# 150555-1-Platino-v1_4.net
KiCad netlist of a schematic drawn in EAGLE
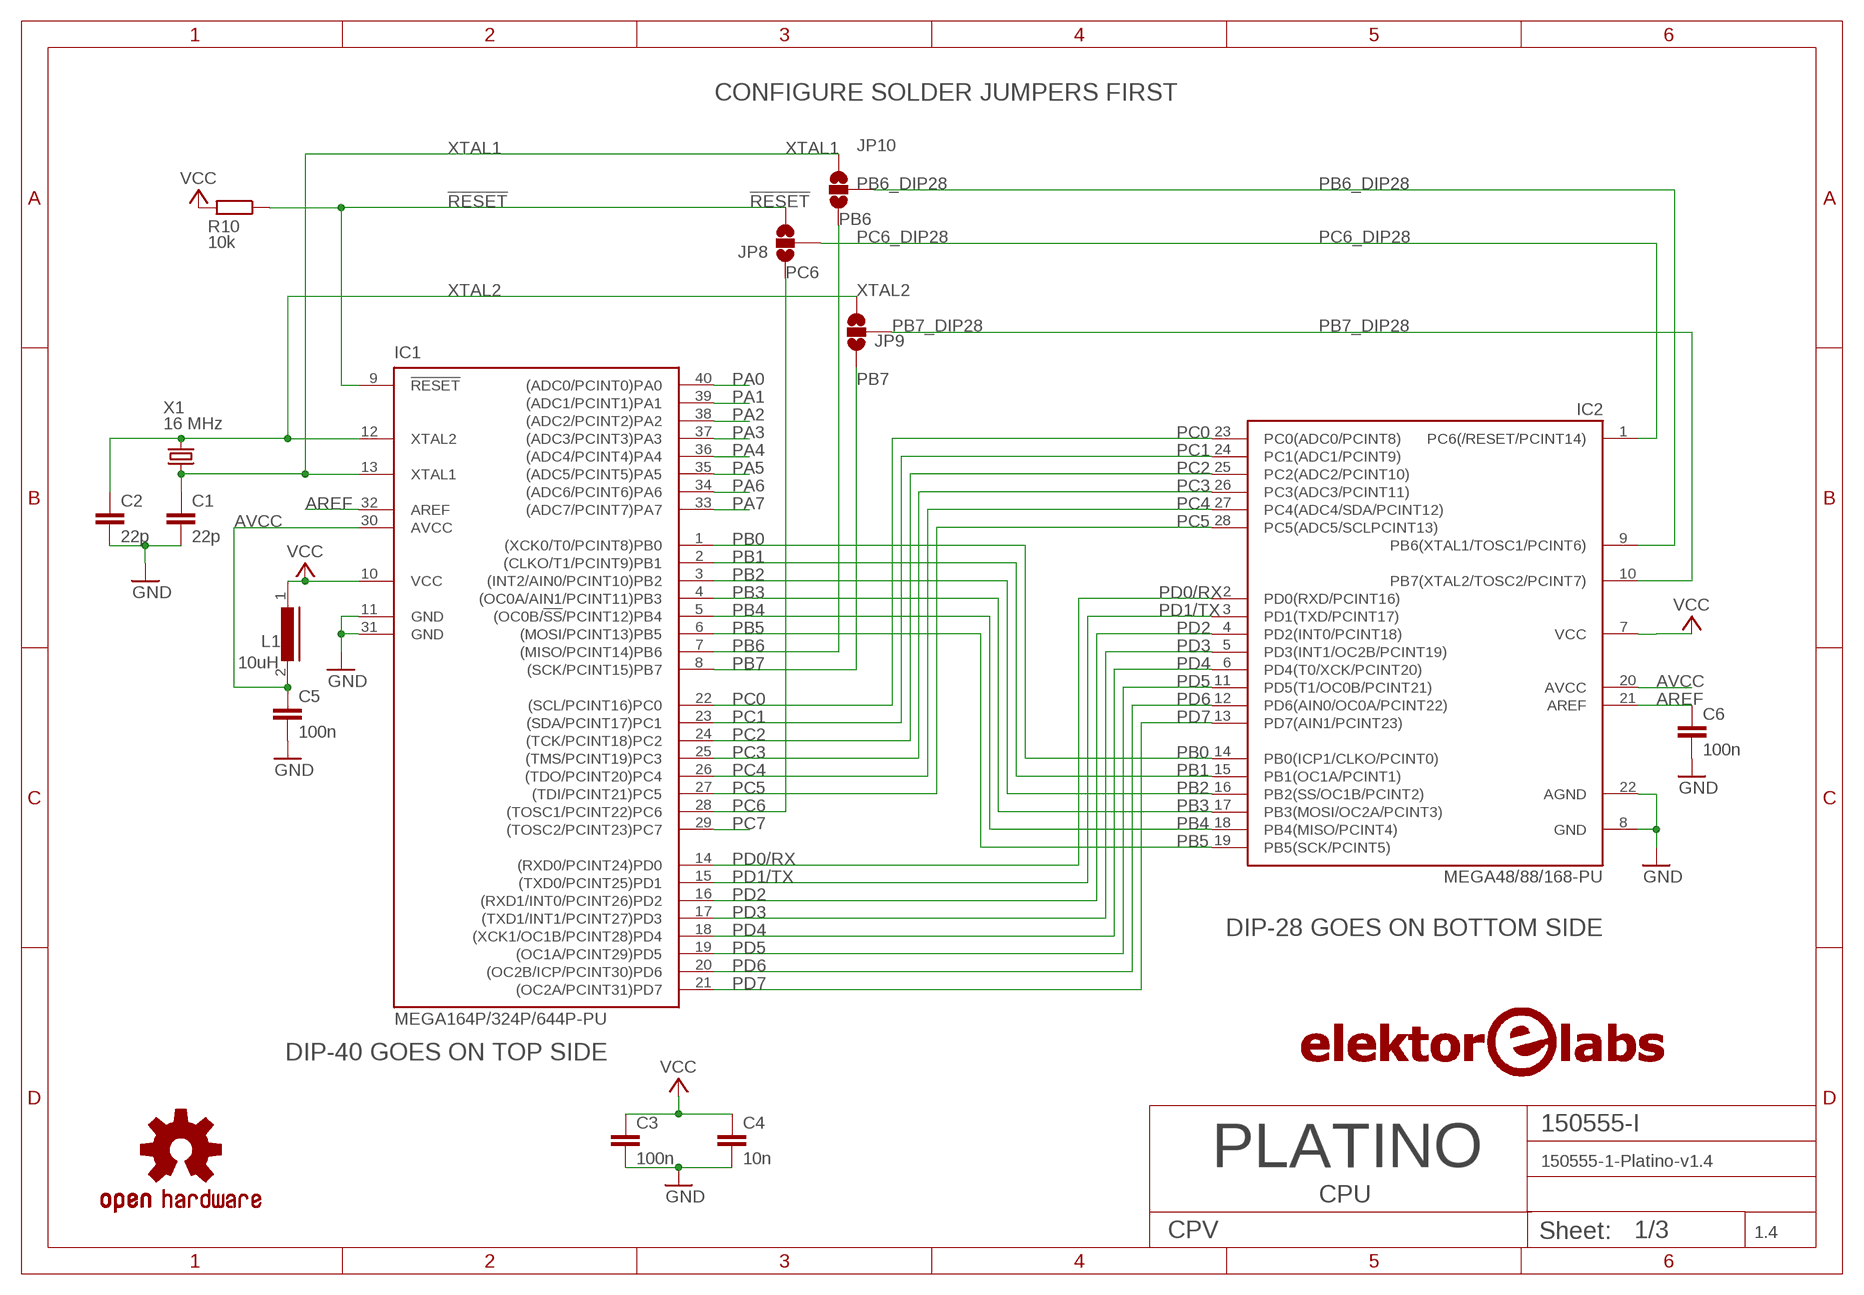
[diagram p0: schematic, sheet 1]
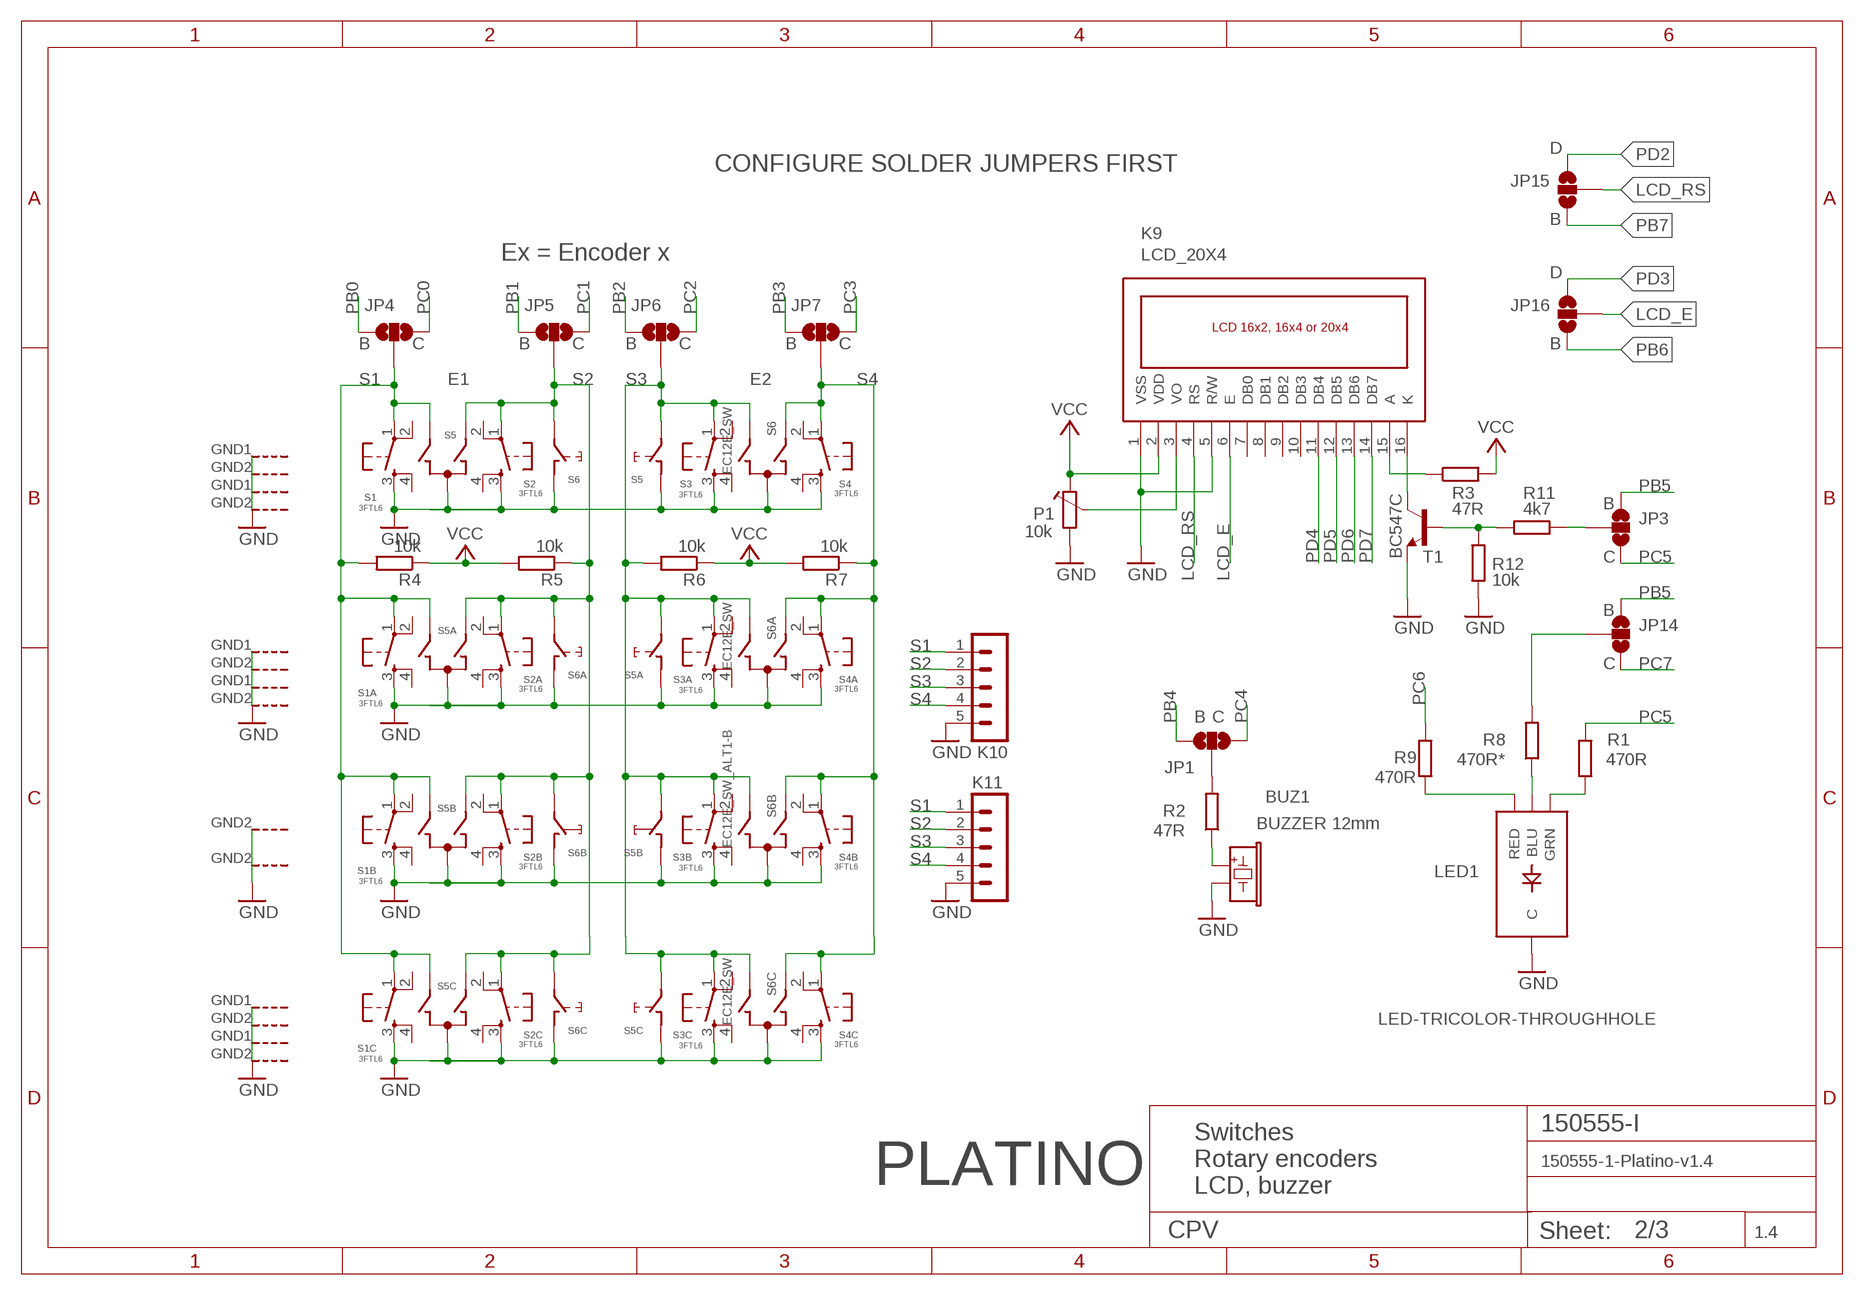
[diagram p1: schematic, sheet 2]
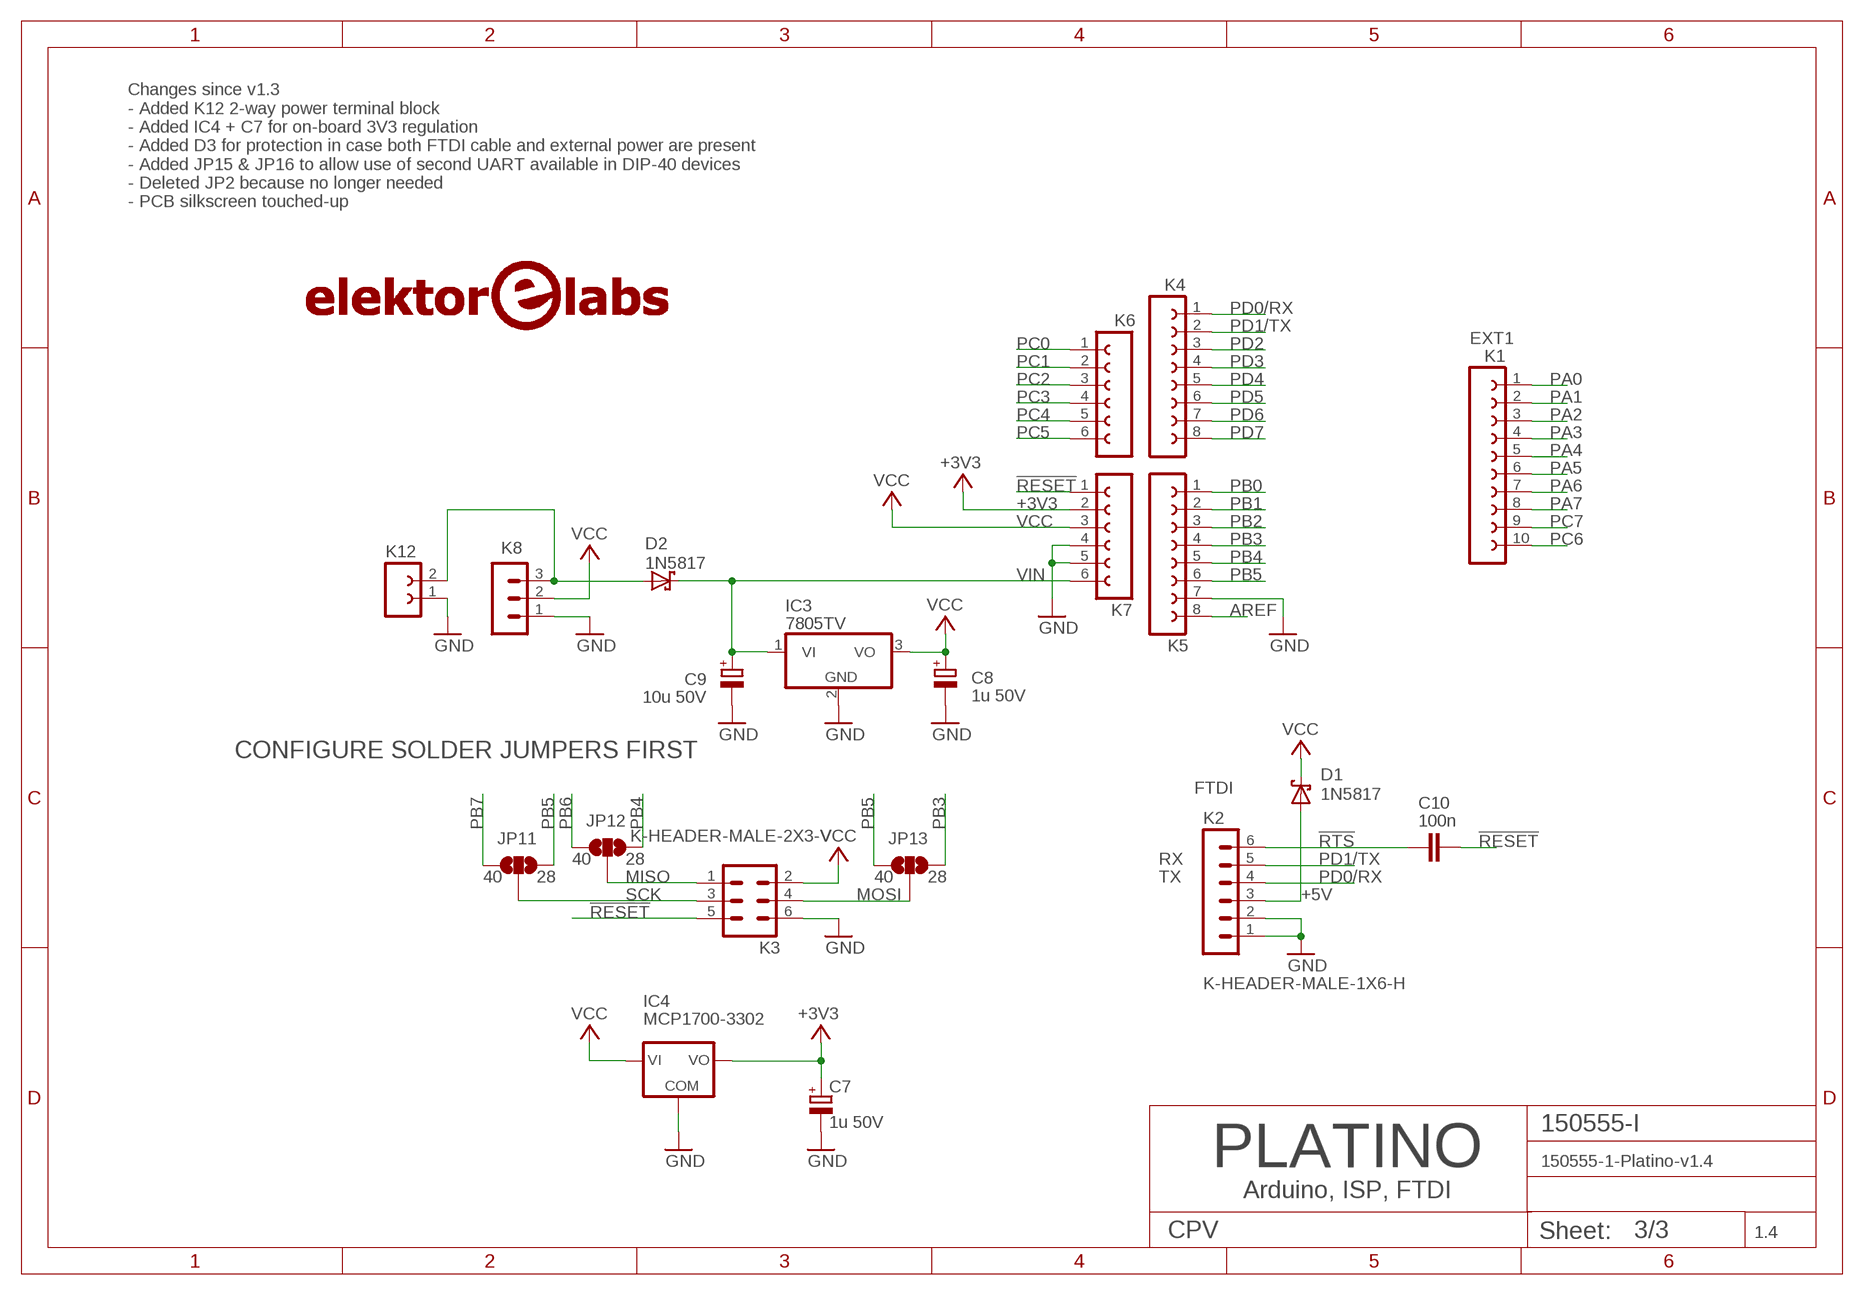
[diagram p2: schematic, sheet 3]

(export (version "E")
  (design (tool "Eeschema 10.0.6"))
  (components
    (comp (ref "C1")
      (value "22p")
      (footprint "eagle-import:ELPP-CNP-250")
      (libsource (lib "eagle-import") (part "C-NP--2.5MM22PF"))
    )
    (comp (ref "C2")
      (value "22p")
      (footprint "eagle-import:ELPP-CNP-250")
      (libsource (lib "eagle-import") (part "C-NP--2.5MM22PF"))
    )
    (comp (ref "C3")
      (value "100n")
      (footprint "eagle-import:ELPP-CNP-508")
      (libsource (lib "eagle-import") (part "C-NP--5.08MM100NF"))
    )
    (comp (ref "C4")
      (value "10n")
      (footprint "eagle-import:ELPP-CNP-254")
      (libsource (lib "eagle-import") (part "C-NP--2.54MM10NF"))
    )
    (comp (ref "C5")
      (value "100n")
      (footprint "eagle-import:ELPP-CNP-508")
      (libsource (lib "eagle-import") (part "C-NP--5.08MM100NF"))
    )
    (comp (ref "C6")
      (value "100n")
      (footprint "eagle-import:ELPP-CNP-508")
      (libsource (lib "eagle-import") (part "C-NP--5.08MM100NF"))
    )
    (comp (ref "IC1")
      (value "MEGA164P/324P/644P-PU")
      (footprint "eagle-import:DIL40")
      (libsource (lib "eagle-import") (part "MEGA164P/324P/644P-PU"))
    )
    (comp (ref "IC2")
      (value "MEGA48/88/168-PU")
      (footprint "eagle-import:DIL28-3")
      (libsource (lib "eagle-import") (part "MEGA48/88/168-PU"))
    )
    (comp (ref "JP8")
      (value "SOLDERJUMPER_2WAYT")
      (footprint "eagle-import:SJ_2")
      (libsource (lib "eagle-import") (part "SOLDERJUMPER_2WAYT"))
    )
    (comp (ref "JP9")
      (value "SOLDERJUMPER_2WAYT")
      (footprint "eagle-import:SJ_2")
      (libsource (lib "eagle-import") (part "SOLDERJUMPER_2WAYT"))
    )
    (comp (ref "JP10")
      (value "SOLDERJUMPER_2WAYT")
      (footprint "eagle-import:SJ_2")
      (libsource (lib "eagle-import") (part "SOLDERJUMPER_2WAYT"))
    )
    (comp (ref "L1")
      (value "10uH")
      (footprint "eagle-import:ELPP-L-0207-1000")
      (libsource (lib "eagle-import") (part "L--10MM10UH"))
    )
    (comp (ref "LOGO2")
      (value "LOGO-ELEKTOR-LABS-25MM")
      (footprint "eagle-import:EPP-LOGO-ELEKTOR-LABS-25MM")
      (libsource (lib "eagle-import") (part "LOGO-ELEKTOR-LABS-25MM"))
    )
    (comp (ref "R10")
      (value "10k")
      (footprint "eagle-import:ELPP-R-0207-1000")
      (libsource (lib "eagle-import") (part "R--10MM10K"))
    )
    (comp (ref "U$2")
      (value "OSHW-LOGOM")
      (footprint "eagle-import:OSHW-LOGO-M")
      (libsource (lib "eagle-import") (part "OSHW-LOGOM"))
    )
    (comp (ref "X1")
      (value "16 MHz")
      (footprint "eagle-import:ELPP-HC49")
      (libsource (lib "eagle-import") (part "X-CRYSTAL--16MHZ"))
    )
    (comp (ref "BUZ1")
      (value "BUZZER 12mm")
      (footprint "eagle-import:ELPP-BUZZER-12MM")
      (libsource (lib "eagle-import") (part "BUZ-BUZZER-12MM"))
    )
    (comp (ref "JP1")
      (value "SOLDERJUMPER_2WAYT")
      (footprint "eagle-import:SJ_2")
      (libsource (lib "eagle-import") (part "SOLDERJUMPER_2WAYT"))
    )
    (comp (ref "JP3")
      (value "SOLDERJUMPER_2WAYT")
      (footprint "eagle-import:SJ_2")
      (libsource (lib "eagle-import") (part "SOLDERJUMPER_2WAYT"))
    )
    (comp (ref "JP4")
      (value "SOLDERJUMPER_2WAYT")
      (footprint "eagle-import:SJ_2")
      (libsource (lib "eagle-import") (part "SOLDERJUMPER_2WAYT"))
    )
    (comp (ref "JP5")
      (value "SOLDERJUMPER_2WAYT")
      (footprint "eagle-import:SJ_2")
      (libsource (lib "eagle-import") (part "SOLDERJUMPER_2WAYT"))
    )
    (comp (ref "JP6")
      (value "SOLDERJUMPER_2WAYT")
      (footprint "eagle-import:SJ_2")
      (libsource (lib "eagle-import") (part "SOLDERJUMPER_2WAYT"))
    )
    (comp (ref "JP7")
      (value "SOLDERJUMPER_2WAYT")
      (footprint "eagle-import:SJ_2")
      (libsource (lib "eagle-import") (part "SOLDERJUMPER_2WAYT"))
    )
    (comp (ref "JP14")
      (value "SOLDERJUMPER_2WAYT")
      (footprint "eagle-import:SJ_2")
      (libsource (lib "eagle-import") (part "SOLDERJUMPER_2WAYT"))
    )
    (comp (ref "JP15")
      (value "SOLDERJUMPER_2WAYT")
      (footprint "eagle-import:SJ_2")
      (libsource (lib "eagle-import") (part "SOLDERJUMPER_2WAYT"))
    )
    (comp (ref "JP16")
      (value "SOLDERJUMPER_2WAYT")
      (footprint "eagle-import:SJ_2")
      (libsource (lib "eagle-import") (part "SOLDERJUMPER_2WAYT"))
    )
    (comp (ref "K9")
      (value "LCD_20X4")
      (footprint "eagle-import:LCD_MULTI2")
      (libsource (lib "eagle-import") (part "LCD_MULTI2"))
    )
    (comp (ref "K10")
      (value "K-HEADER-MALE-1X5-V")
      (footprint "eagle-import:ELPP-SIL-M-5-WAY")
      (libsource (lib "eagle-import") (part "K-HEADER-MALE-1X5-V"))
    )
    (comp (ref "K11")
      (value "K-HEADER-MALE-1X5-V")
      (footprint "eagle-import:ELPP-SIL-M-5-WAY")
      (libsource (lib "eagle-import") (part "K-HEADER-MALE-1X5-V"))
    )
    (comp (ref "LED1")
      (value "LED-TRICOLOR-THROUGHHOLE")
      (footprint "eagle-import:LED-TRICOLOR-THROUGHHOLE")
      (libsource (lib "eagle-import") (part "LED-TRICOLOR-THROUGHHOLE"))
    )
    (comp (ref "P1")
      (value "10k")
      (footprint "eagle-import:ELPP-TRIMMER-CB10-H")
      (libsource (lib "eagle-import") (part "P-TRIMMER--PT-1010K"))
    )
    (comp (ref "R1")
      (value "470R")
      (footprint "eagle-import:ELPP-R-0207-1000")
      (libsource (lib "eagle-import") (part "R--10MM470R"))
    )
    (comp (ref "R2")
      (value "47R")
      (footprint "eagle-import:ELPP-R-0207-1000")
      (libsource (lib "eagle-import") (part "R--10MM47R"))
    )
    (comp (ref "R3")
      (value "47R")
      (footprint "eagle-import:ELPP-R-0207-1000")
      (libsource (lib "eagle-import") (part "R--10MM47R"))
    )
    (comp (ref "R4")
      (value "10k")
      (footprint "eagle-import:ELPP-R-0207-1000")
      (libsource (lib "eagle-import") (part "R--10MM10K"))
    )
    (comp (ref "R5")
      (value "10k")
      (footprint "eagle-import:ELPP-R-0207-1000")
      (libsource (lib "eagle-import") (part "R--10MM10K"))
    )
    (comp (ref "R6")
      (value "10k")
      (footprint "eagle-import:ELPP-R-0207-1000")
      (libsource (lib "eagle-import") (part "R--10MM10K"))
    )
    (comp (ref "R7")
      (value "10k")
      (footprint "eagle-import:ELPP-R-0207-1000")
      (libsource (lib "eagle-import") (part "R--10MM10K"))
    )
    (comp (ref "R8")
      (value "470R*")
      (footprint "eagle-import:ELPP-R-0207-1000")
      (libsource (lib "eagle-import") (part "R--10MM470R"))
    )
    (comp (ref "R9")
      (value "470R")
      (footprint "eagle-import:ELPP-R-0207-1000")
      (libsource (lib "eagle-import") (part "R--10MM470R"))
    )
    (comp (ref "R11")
      (value "4k7")
      (footprint "eagle-import:ELPP-R-0207-1000")
      (libsource (lib "eagle-import") (part "R--10MM4K7"))
    )
    (comp (ref "R12")
      (value "10k")
      (footprint "eagle-import:ELPP-R-0207-1000")
      (libsource (lib "eagle-import") (part "R--10MM10K"))
    )
    (comp (ref "S1")
      (value "3FTL6")
      (footprint "eagle-import:PUSHBUTTON_MULTIMEC")
      (libsource (lib "eagle-import") (part "PUSHBUTTON_MULTIMEC"))
    )
    (comp (ref "S1A")
      (value "3FTL6")
      (footprint "eagle-import:PUSHBUTTON_MULTIMEC")
      (libsource (lib "eagle-import") (part "PUSHBUTTON_MULTIMEC"))
    )
    (comp (ref "S1B")
      (value "3FTL6")
      (footprint "eagle-import:PUSHBUTTON_MULTIMEC")
      (libsource (lib "eagle-import") (part "PUSHBUTTON_MULTIMEC"))
    )
    (comp (ref "S1C")
      (value "3FTL6")
      (footprint "eagle-import:PUSHBUTTON_MULTIMEC")
      (libsource (lib "eagle-import") (part "PUSHBUTTON_MULTIMEC"))
    )
    (comp (ref "S2")
      (value "3FTL6")
      (footprint "eagle-import:PUSHBUTTON_MULTIMEC")
      (libsource (lib "eagle-import") (part "PUSHBUTTON_MULTIMEC"))
    )
    (comp (ref "S2A")
      (value "3FTL6")
      (footprint "eagle-import:PUSHBUTTON_MULTIMEC")
      (libsource (lib "eagle-import") (part "PUSHBUTTON_MULTIMEC"))
    )
    (comp (ref "S2B")
      (value "3FTL6")
      (footprint "eagle-import:PUSHBUTTON_MULTIMEC")
      (libsource (lib "eagle-import") (part "PUSHBUTTON_MULTIMEC"))
    )
    (comp (ref "S2C")
      (value "3FTL6")
      (footprint "eagle-import:PUSHBUTTON_MULTIMEC")
      (libsource (lib "eagle-import") (part "PUSHBUTTON_MULTIMEC"))
    )
    (comp (ref "S3")
      (value "3FTL6")
      (footprint "eagle-import:PUSHBUTTON_MULTIMEC")
      (libsource (lib "eagle-import") (part "PUSHBUTTON_MULTIMEC"))
    )
    (comp (ref "S3A")
      (value "3FTL6")
      (footprint "eagle-import:PUSHBUTTON_MULTIMEC")
      (libsource (lib "eagle-import") (part "PUSHBUTTON_MULTIMEC"))
    )
    (comp (ref "S3B")
      (value "3FTL6")
      (footprint "eagle-import:PUSHBUTTON_MULTIMEC")
      (libsource (lib "eagle-import") (part "PUSHBUTTON_MULTIMEC"))
    )
    (comp (ref "S3C")
      (value "3FTL6")
      (footprint "eagle-import:PUSHBUTTON_MULTIMEC")
      (libsource (lib "eagle-import") (part "PUSHBUTTON_MULTIMEC"))
    )
    (comp (ref "S4")
      (value "3FTL6")
      (footprint "eagle-import:PUSHBUTTON_MULTIMEC")
      (libsource (lib "eagle-import") (part "PUSHBUTTON_MULTIMEC"))
    )
    (comp (ref "S4A")
      (value "3FTL6")
      (footprint "eagle-import:PUSHBUTTON_MULTIMEC")
      (libsource (lib "eagle-import") (part "PUSHBUTTON_MULTIMEC"))
    )
    (comp (ref "S4B")
      (value "3FTL6")
      (footprint "eagle-import:PUSHBUTTON_MULTIMEC")
      (libsource (lib "eagle-import") (part "PUSHBUTTON_MULTIMEC"))
    )
    (comp (ref "S4C")
      (value "3FTL6")
      (footprint "eagle-import:PUSHBUTTON_MULTIMEC")
      (libsource (lib "eagle-import") (part "PUSHBUTTON_MULTIMEC"))
    )
    (comp (ref "S5")
      (value "EC12E_SW")
      (footprint "eagle-import:ALPS_EC12E_SW")
      (fields (field (name "MPN") "EC12E2424407"))
      (libsource (lib "eagle-import") (part "EC12E_SW"))
    )
    (comp (ref "S5A")
      (value "EC12E_SW")
      (footprint "eagle-import:ALPS_EC12E_SW")
      (fields (field (name "MPN") "EC12E2424407"))
      (libsource (lib "eagle-import") (part "EC12E_SW"))
    )
    (comp (ref "S5B")
      (value "EC12E_SW_ALT1-B")
      (footprint "eagle-import:ALPS_EC12E_SW_ALT2")
      (libsource (lib "eagle-import") (part "EC12E_SW_ALT1-B"))
    )
    (comp (ref "S5C")
      (value "EC12E_SW")
      (footprint "eagle-import:ALPS_EC12E_SW")
      (fields (field (name "MPN") "EC12E2424407"))
      (libsource (lib "eagle-import") (part "EC12E_SW"))
    )
    (comp (ref "S6")
      (value "EC12E_SW")
      (footprint "eagle-import:ALPS_EC12E_SW")
      (fields (field (name "MPN") "EC12E2424407"))
      (libsource (lib "eagle-import") (part "EC12E_SW"))
    )
    (comp (ref "S6A")
      (value "EC12E_SW")
      (footprint "eagle-import:ALPS_EC12E_SW")
      (fields (field (name "MPN") "EC12E2424407"))
      (libsource (lib "eagle-import") (part "EC12E_SW"))
    )
    (comp (ref "S6B")
      (value "EC12E_SW_ALT1-B")
      (footprint "eagle-import:ALPS_EC12E_SW_ALT2")
      (libsource (lib "eagle-import") (part "EC12E_SW_ALT1-B"))
    )
    (comp (ref "S6C")
      (value "EC12E_SW")
      (footprint "eagle-import:ALPS_EC12E_SW")
      (fields (field (name "MPN") "EC12E2424407"))
      (libsource (lib "eagle-import") (part "EC12E_SW"))
    )
    (comp (ref "T1")
      (value "BC547C")
      (footprint "eagle-import:TO-92")
      (libsource (lib "eagle-import") (part "TRANSISTOR_NPNTO92"))
    )
    (comp (ref "C7")
      (value "1u 50V")
      (footprint "eagle-import:ELPP-CP-200-500")
      (libsource (lib "eagle-import") (part "C-POL--200-5001UF"))
    )
    (comp (ref "C8")
      (value "1u 50V")
      (footprint "eagle-import:ELPP-CP-200-500")
      (libsource (lib "eagle-import") (part "C-POL--200-5001UF"))
    )
    (comp (ref "C9")
      (value "10u 50V")
      (footprint "eagle-import:ELPP-CP-200-500")
      (libsource (lib "eagle-import") (part "C-POL--200-50010UF"))
    )
    (comp (ref "C10")
      (value "100n")
      (footprint "eagle-import:ELPP-CNP-508")
      (libsource (lib "eagle-import") (part "C-NP--5.08MM100NF"))
    )
    (comp (ref "D1")
      (value "1N5817")
      (footprint "eagle-import:ELPP-DO-41")
      (libsource (lib "eagle-import") (part "D-SCHOTTKY--D0411N5817"))
    )
    (comp (ref "D2")
      (value "1N5817")
      (footprint "eagle-import:ELPP-DO-41")
      (libsource (lib "eagle-import") (part "D-SCHOTTKY--D0411N5817"))
    )
    (comp (ref "IC3")
      (value "7805TV")
      (footprint "eagle-import:TO220V")
      (libsource (lib "eagle-import") (part "78TV05"))
    )
    (comp (ref "IC4")
      (value "MCP1700-3302")
      (footprint "eagle-import:ELPP-TO-92")
      (libsource (lib "eagle-import") (part "IC-REGULATOR--MCP17003V3"))
    )
    (comp (ref "JP11")
      (value "SOLDERJUMPER_2WAYT")
      (footprint "eagle-import:SJ_2")
      (libsource (lib "eagle-import") (part "SOLDERJUMPER_2WAYT"))
    )
    (comp (ref "JP12")
      (value "SOLDERJUMPER_2WAYT")
      (footprint "eagle-import:SJ_2")
      (libsource (lib "eagle-import") (part "SOLDERJUMPER_2WAYT"))
    )
    (comp (ref "JP13")
      (value "SOLDERJUMPER_2WAYT")
      (footprint "eagle-import:SJ_2")
      (libsource (lib "eagle-import") (part "SOLDERJUMPER_2WAYT"))
    )
    (comp (ref "K1")
      (value "EXT1")
      (footprint "eagle-import:ELPP-SIL-F-10-WAY")
      (libsource (lib "eagle-import") (part "K-HEADER-FEMALE-1X10-V"))
    )
    (comp (ref "K2")
      (value "K-HEADER-MALE-1X6-H")
      (footprint "eagle-import:ELPP-SIL-M-6-WAY-90DEG")
      (libsource (lib "eagle-import") (part "K-HEADER-MALE-1X6-H"))
    )
    (comp (ref "K3")
      (value "K-HEADER-MALE-2X3-V")
      (footprint "eagle-import:ELPP-DIL-M-6-WAY-V")
      (libsource (lib "eagle-import") (part "K-HEADER-MALE-2X3-V"))
    )
    (comp (ref "K4")
      (value "K-HEADER-FEMALE-1X8-V")
      (footprint "eagle-import:ELPP-SIL-F-8-WAY")
      (libsource (lib "eagle-import") (part "K-HEADER-FEMALE-1X8-V"))
    )
    (comp (ref "K5")
      (value "K-HEADER-FEMALE-1X8-V")
      (footprint "eagle-import:ELPP-SIL-F-8-WAY")
      (libsource (lib "eagle-import") (part "K-HEADER-FEMALE-1X8-V"))
    )
    (comp (ref "K6")
      (value "K-HEADER-FEMALE-1X6-V")
      (footprint "eagle-import:ELPP-SIL-F-6-WAY")
      (libsource (lib "eagle-import") (part "K-HEADER-FEMALE-1X6-V"))
    )
    (comp (ref "K7")
      (value "K-HEADER-FEMALE-1X6-V")
      (footprint "eagle-import:ELPP-SIL-F-6-WAY")
      (libsource (lib "eagle-import") (part "K-HEADER-FEMALE-1X6-V"))
    )
    (comp (ref "K8")
      (value "K-HEADER-MALE-1X3-V")
      (footprint "eagle-import:ELPP-SIL-M-3-WAY")
      (libsource (lib "eagle-import") (part "K-HEADER-MALE-1X3-V"))
    )
    (comp (ref "K12")
      (value "K-TERMINAL-BLOCK-1X2-350")
      (footprint "eagle-import:ELPP-TB-350-2")
      (libsource (lib "eagle-import") (part "K-TERMINAL-BLOCK-1X2-350"))
    )
    (comp (ref "LOGO1")
      (value "LOGO-ELEKTOR-LABS-25MM")
      (footprint "eagle-import:EPP-LOGO-ELEKTOR-LABS-25MM")
      (libsource (lib "eagle-import") (part "LOGO-ELEKTOR-LABS-25MM"))
    )
  )
  (nets
    (net (code "1") (name "+3V3") (class "Default")
      (node (ref "C7") (pin "+") (pinfunction "+_+") (pintype "passive"))
      (node (ref "IC4") (pin "3") (pinfunction "VO_3") (pintype "passive"))
      (node (ref "K7") (pin "2") (pinfunction "2_2") (pintype "passive"))
    )
    (net (code "2") (name "+5V") (class "Default")
      (node (ref "D1") (pin "A") (pinfunction "A_A") (pintype "passive"))
      (node (ref "K2") (pin "3") (pinfunction "3_3") (pintype "passive"))
    )
    (net (code "3") (name "AREF") (class "Default")
      (node (ref "C6") (pin "1") (pinfunction "1_1") (pintype "passive"))
      (node (ref "IC1") (pin "32") (pinfunction "AREF_32") (pintype "power_in"))
      (node (ref "IC2") (pin "21") (pinfunction "AREF_21") (pintype "passive"))
      (node (ref "K5") (pin "8") (pinfunction "8_8") (pintype "passive"))
    )
    (net (code "4") (name "AVCC") (class "Default")
      (node (ref "C5") (pin "1") (pinfunction "1_1") (pintype "passive"))
      (node (ref "IC1") (pin "30") (pinfunction "AVCC_30") (pintype "power_in"))
      (node (ref "IC2") (pin "20") (pinfunction "AVCC_20") (pintype "passive"))
      (node (ref "L1") (pin "2") (pinfunction "2_2") (pintype "passive"))
    )
    (net (code "5") (name "GND") (class "Default")
      (node (ref "BUZ1") (pin "-") (pinfunction "2_-") (pintype "passive"))
      (node (ref "C1") (pin "2") (pinfunction "2_2") (pintype "passive"))
      (node (ref "C2") (pin "2") (pinfunction "2_2") (pintype "passive"))
      (node (ref "C3") (pin "2") (pinfunction "2_2") (pintype "passive"))
      (node (ref "C4") (pin "2") (pinfunction "2_2") (pintype "passive"))
      (node (ref "C5") (pin "2") (pinfunction "2_2") (pintype "passive"))
      (node (ref "C6") (pin "2") (pinfunction "2_2") (pintype "passive"))
      (node (ref "C7") (pin "-") (pinfunction "-_-") (pintype "passive"))
      (node (ref "C8") (pin "-") (pinfunction "-_-") (pintype "passive"))
      (node (ref "C9") (pin "-") (pinfunction "-_-") (pintype "passive"))
      (node (ref "IC1") (pin "11") (pinfunction "GND_11") (pintype "power_in"))
      (node (ref "IC1") (pin "31") (pinfunction "GND_31") (pintype "power_in"))
      (node (ref "IC2") (pin "22") (pinfunction "AGND_22") (pintype "power_in"))
      (node (ref "IC2") (pin "8") (pinfunction "GND_8") (pintype "power_in"))
      (node (ref "IC3") (pin "2") (pinfunction "GND_2") (pintype "passive"))
      (node (ref "IC4") (pin "1") (pinfunction "COM_1") (pintype "input"))
      (node (ref "K10") (pin "5") (pinfunction "5_5") (pintype "passive"))
      (node (ref "K11") (pin "5") (pinfunction "5_5") (pintype "passive"))
      (node (ref "K12") (pin "1") (pinfunction "1_1") (pintype "passive"))
      (node (ref "K2") (pin "1") (pinfunction "1_1") (pintype "passive"))
      (node (ref "K2") (pin "2") (pinfunction "2_2") (pintype "passive"))
      (node (ref "K3") (pin "6") (pinfunction "6_6") (pintype "passive"))
      (node (ref "K5") (pin "7") (pinfunction "7_7") (pintype "passive"))
      (node (ref "K7") (pin "4") (pinfunction "4_4") (pintype "passive"))
      (node (ref "K7") (pin "5") (pinfunction "5_5") (pintype "passive"))
      (node (ref "K8") (pin "1") (pinfunction "1_1") (pintype "passive"))
      (node (ref "K9") (pin "1") (pinfunction "VSS_1") (pintype "power_in"))
      (node (ref "K9") (pin "5") (pinfunction "R/W_5") (pintype "input"))
      (node (ref "LED1") (pin "GND") (pinfunction "C_GND") (pintype "bidirectional"))
      (node (ref "P1") (pin "1") (pinfunction "1_1") (pintype "passive"))
      (node (ref "R12") (pin "1") (pinfunction "1_1") (pintype "passive"))
      (node (ref "S1") (pin "3") (pinfunction "3_3") (pintype "passive"))
      (node (ref "S1A") (pin "3") (pinfunction "3_3") (pintype "passive"))
      (node (ref "S1B") (pin "3") (pinfunction "3_3") (pintype "passive"))
      (node (ref "S1C") (pin "3") (pinfunction "3_3") (pintype "passive"))
      (node (ref "S2") (pin "3") (pinfunction "3_3") (pintype "passive"))
      (node (ref "S2A") (pin "3") (pinfunction "3_3") (pintype "passive"))
      (node (ref "S2B") (pin "3") (pinfunction "3_3") (pintype "passive"))
      (node (ref "S2C") (pin "3") (pinfunction "3_3") (pintype "passive"))
      (node (ref "S3") (pin "3") (pinfunction "3_3") (pintype "passive"))
      (node (ref "S3A") (pin "3") (pinfunction "3_3") (pintype "passive"))
      (node (ref "S3B") (pin "3") (pinfunction "3_3") (pintype "passive"))
      (node (ref "S3C") (pin "3") (pinfunction "3_3") (pintype "passive"))
      (node (ref "S4") (pin "3") (pinfunction "3_3") (pintype "passive"))
      (node (ref "S4A") (pin "3") (pinfunction "3_3") (pintype "passive"))
      (node (ref "S4B") (pin "3") (pinfunction "3_3") (pintype "passive"))
      (node (ref "S4C") (pin "3") (pinfunction "3_3") (pintype "passive"))
      (node (ref "S5") (pin "C") (pinfunction "C_C") (pintype "passive"))
      (node (ref "S5") (pin "D") (pinfunction "1_D") (pintype "passive"))
      (node (ref "S5") (pin "GND1") (pinfunction "G_GND1") (pintype "passive"))
      (node (ref "S5") (pin "GND2") (pinfunction "G_GND2") (pintype "passive"))
      (node (ref "S5A") (pin "C") (pinfunction "C_C") (pintype "passive"))
      (node (ref "S5A") (pin "D") (pinfunction "1_D") (pintype "passive"))
      (node (ref "S5A") (pin "GND1") (pinfunction "G_GND1") (pintype "passive"))
      (node (ref "S5A") (pin "GND2") (pinfunction "G_GND2") (pintype "passive"))
      (node (ref "S5B") (pin "C") (pinfunction "C_C") (pintype "passive"))
      (node (ref "S5B") (pin "D") (pinfunction "1_D") (pintype "passive"))
      (node (ref "S5B") (pin "GND2") (pinfunction "G_GND2") (pintype "passive"))
      (node (ref "S5C") (pin "C") (pinfunction "C_C") (pintype "passive"))
      (node (ref "S5C") (pin "D") (pinfunction "1_D") (pintype "passive"))
      (node (ref "S5C") (pin "GND1") (pinfunction "G_GND1") (pintype "passive"))
      (node (ref "S5C") (pin "GND2") (pinfunction "G_GND2") (pintype "passive"))
      (node (ref "S6") (pin "C") (pinfunction "C_C") (pintype "passive"))
      (node (ref "S6") (pin "D") (pinfunction "1_D") (pintype "passive"))
      (node (ref "S6") (pin "GND1") (pinfunction "G_GND1") (pintype "passive"))
      (node (ref "S6") (pin "GND2") (pinfunction "G_GND2") (pintype "passive"))
      (node (ref "S6A") (pin "C") (pinfunction "C_C") (pintype "passive"))
      (node (ref "S6A") (pin "D") (pinfunction "1_D") (pintype "passive"))
      (node (ref "S6A") (pin "GND1") (pinfunction "G_GND1") (pintype "passive"))
      (node (ref "S6A") (pin "GND2") (pinfunction "G_GND2") (pintype "passive"))
      (node (ref "S6B") (pin "C") (pinfunction "C_C") (pintype "passive"))
      (node (ref "S6B") (pin "D") (pinfunction "1_D") (pintype "passive"))
      (node (ref "S6B") (pin "GND2") (pinfunction "G_GND2") (pintype "passive"))
      (node (ref "S6C") (pin "C") (pinfunction "C_C") (pintype "passive"))
      (node (ref "S6C") (pin "D") (pinfunction "1_D") (pintype "passive"))
      (node (ref "S6C") (pin "GND1") (pinfunction "G_GND1") (pintype "passive"))
      (node (ref "S6C") (pin "GND2") (pinfunction "G_GND2") (pintype "passive"))
      (node (ref "T1") (pin "1") (pinfunction "E_1") (pintype "passive"))
    )
    (net (code "6") (name "LCD_E") (class "Default")
      (node (ref "JP16") (pin "2") (pinfunction "2_2") (pintype "passive"))
      (node (ref "K9") (pin "6") (pinfunction "E_6") (pintype "input"))
    )
    (net (code "7") (name "LCD_RS") (class "Default")
      (node (ref "JP15") (pin "2") (pinfunction "2_2") (pintype "passive"))
      (node (ref "K9") (pin "4") (pinfunction "RS_4") (pintype "input"))
    )
    (net (code "8") (name "MISO") (class "Default")
      (node (ref "JP12") (pin "2") (pinfunction "2_2") (pintype "passive"))
      (node (ref "K3") (pin "1") (pinfunction "1_1") (pintype "passive"))
    )
    (net (code "9") (name "MOSI") (class "Default")
      (node (ref "JP13") (pin "2") (pinfunction "2_2") (pintype "passive"))
      (node (ref "K3") (pin "4") (pinfunction "4_4") (pintype "passive"))
    )
    (net (code "10") (name "Net-(BUZ1-1)") (class "Default")
      (node (ref "BUZ1") (pin "+") (pinfunction "1_+") (pintype "passive"))
      (node (ref "R2") (pin "1") (pinfunction "1_1") (pintype "passive"))
    )
    (net (code "11") (name "Net-(D2-PadA)") (class "Default")
      (node (ref "D2") (pin "A") (pinfunction "A_A") (pintype "passive"))
      (node (ref "K12") (pin "2") (pinfunction "2_2") (pintype "passive"))
      (node (ref "K8") (pin "3") (pinfunction "3_3") (pintype "passive"))
    )
    (net (code "12") (name "Net-(JP1-Pad2)") (class "Default")
      (node (ref "JP1") (pin "2") (pinfunction "2_2") (pintype "passive"))
      (node (ref "R2") (pin "2") (pinfunction "2_2") (pintype "passive"))
    )
    (net (code "13") (name "Net-(JP3-Pad2)") (class "Default")
      (node (ref "JP3") (pin "2") (pinfunction "2_2") (pintype "passive"))
      (node (ref "R11") (pin "2") (pinfunction "2_2") (pintype "passive"))
    )
    (net (code "14") (name "Net-(JP14-Pad2)") (class "Default")
      (node (ref "JP14") (pin "2") (pinfunction "2_2") (pintype "passive"))
      (node (ref "R8") (pin "2") (pinfunction "2_2") (pintype "passive"))
    )
    (net (code "15") (name "Net-(K9-A)") (class "Default")
      (node (ref "K9") (pin "15") (pinfunction "A_15") (pintype "passive"))
      (node (ref "R3") (pin "1") (pinfunction "1_1") (pintype "passive"))
    )
    (net (code "16") (name "Net-(K9-K)") (class "Default")
      (node (ref "K9") (pin "16") (pinfunction "K_16") (pintype "passive"))
      (node (ref "T1") (pin "3") (pinfunction "C_3") (pintype "passive"))
    )
    (net (code "17") (name "Net-(K9-VO)") (class "Default")
      (node (ref "K9") (pin "3") (pinfunction "VO_3") (pintype "passive"))
      (node (ref "P1") (pin "3") (pinfunction "3_3") (pintype "passive"))
    )
    (net (code "18") (name "Net-(LED1-PadBLU)") (class "Default")
      (node (ref "LED1") (pin "BLU") (pinfunction "BLU_BLU") (pintype "bidirectional"))
      (node (ref "R8") (pin "1") (pinfunction "1_1") (pintype "passive"))
    )
    (net (code "19") (name "Net-(LED1-PadGRN)") (class "Default")
      (node (ref "LED1") (pin "GRN") (pinfunction "GRN_GRN") (pintype "bidirectional"))
      (node (ref "R1") (pin "1") (pinfunction "1_1") (pintype "passive"))
    )
    (net (code "20") (name "Net-(LED1-PadRED)") (class "Default")
      (node (ref "LED1") (pin "RED") (pinfunction "RED_RED") (pintype "bidirectional"))
      (node (ref "R9") (pin "1") (pinfunction "1_1") (pintype "passive"))
    )
    (net (code "21") (name "Net-(T1-B)") (class "Default")
      (node (ref "R11") (pin "1") (pinfunction "1_1") (pintype "passive"))
      (node (ref "R12") (pin "2") (pinfunction "2_2") (pintype "passive"))
      (node (ref "T1") (pin "2") (pinfunction "B_2") (pintype "passive"))
    )
    (net (code "22") (name "PA0") (class "Default")
      (node (ref "IC1") (pin "40") (pinfunction "(ADC0/PCINT0)PA0_40") (pintype "bidirectional"))
      (node (ref "K1") (pin "1") (pinfunction "1_1") (pintype "passive"))
    )
    (net (code "23") (name "PA1") (class "Default")
      (node (ref "IC1") (pin "39") (pinfunction "(ADC1/PCINT1)PA1_39") (pintype "bidirectional"))
      (node (ref "K1") (pin "2") (pinfunction "2_2") (pintype "passive"))
    )
    (net (code "24") (name "PA2") (class "Default")
      (node (ref "IC1") (pin "38") (pinfunction "(ADC2/PCINT2)PA2_38") (pintype "bidirectional"))
      (node (ref "K1") (pin "3") (pinfunction "3_3") (pintype "passive"))
    )
    (net (code "25") (name "PA3") (class "Default")
      (node (ref "IC1") (pin "37") (pinfunction "(ADC3/PCINT3)PA3_37") (pintype "bidirectional"))
      (node (ref "K1") (pin "4") (pinfunction "4_4") (pintype "passive"))
    )
    (net (code "26") (name "PA4") (class "Default")
      (node (ref "IC1") (pin "36") (pinfunction "(ADC4/PCINT4)PA4_36") (pintype "bidirectional"))
      (node (ref "K1") (pin "5") (pinfunction "5_5") (pintype "passive"))
    )
    (net (code "27") (name "PA5") (class "Default")
      (node (ref "IC1") (pin "35") (pinfunction "(ADC5/PCINT5)PA5_35") (pintype "bidirectional"))
      (node (ref "K1") (pin "6") (pinfunction "6_6") (pintype "passive"))
    )
    (net (code "28") (name "PA6") (class "Default")
      (node (ref "IC1") (pin "34") (pinfunction "(ADC6/PCINT6)PA6_34") (pintype "bidirectional"))
      (node (ref "K1") (pin "7") (pinfunction "7_7") (pintype "passive"))
    )
    (net (code "29") (name "PA7") (class "Default")
      (node (ref "IC1") (pin "33") (pinfunction "(ADC7/PCINT7)PA7_33") (pintype "bidirectional"))
      (node (ref "K1") (pin "8") (pinfunction "8_8") (pintype "passive"))
    )
    (net (code "30") (name "PB0") (class "Default")
      (node (ref "IC1") (pin "1") (pinfunction "(XCK0/T0/PCINT8)PB0_1") (pintype "bidirectional"))
      (node (ref "IC2") (pin "14") (pinfunction "PB0(ICP1/CLKO/PCINT0)_14") (pintype "bidirectional"))
      (node (ref "JP4") (pin "1") (pinfunction "1_1") (pintype "passive"))
      (node (ref "K5") (pin "1") (pinfunction "1_1") (pintype "passive"))
    )
    (net (code "31") (name "PB1") (class "Default")
      (node (ref "IC1") (pin "2") (pinfunction "(CLKO/T1/PCINT9)PB1_2") (pintype "bidirectional"))
      (node (ref "IC2") (pin "15") (pinfunction "PB1(OC1A/PCINT1)_15") (pintype "bidirectional"))
      (node (ref "JP5") (pin "1") (pinfunction "1_1") (pintype "passive"))
      (node (ref "K5") (pin "2") (pinfunction "2_2") (pintype "passive"))
    )
    (net (code "32") (name "PB2") (class "Default")
      (node (ref "IC1") (pin "3") (pinfunction "(INT2/AIN0/PCINT10)PB2_3") (pintype "bidirectional"))
      (node (ref "IC2") (pin "16") (pinfunction "PB2(SS/OC1B/PCINT2)_16") (pintype "bidirectional"))
      (node (ref "JP6") (pin "1") (pinfunction "1_1") (pintype "passive"))
      (node (ref "K5") (pin "3") (pinfunction "3_3") (pintype "passive"))
    )
    (net (code "33") (name "PB3") (class "Default")
      (node (ref "IC1") (pin "4") (pinfunction "(OC0A/AIN1/PCINT11)PB3_4") (pintype "bidirectional"))
      (node (ref "IC2") (pin "17") (pinfunction "PB3(MOSI/OC2A/PCINT3)_17") (pintype "bidirectional"))
      (node (ref "JP13") (pin "3") (pinfunction "3_3") (pintype "passive"))
      (node (ref "JP7") (pin "1") (pinfunction "1_1") (pintype "passive"))
      (node (ref "K5") (pin "4") (pinfunction "4_4") (pintype "passive"))
    )
    (net (code "34") (name "PB4") (class "Default")
      (node (ref "IC1") (pin "5") (pinfunction "(OC0B/~{SS}/PCINT12)PB4_5") (pintype "bidirectional"))
      (node (ref "IC2") (pin "18") (pinfunction "PB4(MISO/PCINT4)_18") (pintype "bidirectional"))
      (node (ref "JP1") (pin "1") (pinfunction "1_1") (pintype "passive"))
      (node (ref "JP12") (pin "3") (pinfunction "3_3") (pintype "passive"))
      (node (ref "K5") (pin "5") (pinfunction "5_5") (pintype "passive"))
    )
    (net (code "35") (name "PB5") (class "Default")
      (node (ref "IC1") (pin "6") (pinfunction "(MOSI/PCINT13)PB5_6") (pintype "bidirectional"))
      (node (ref "IC2") (pin "19") (pinfunction "PB5(SCK/PCINT5)_19") (pintype "bidirectional"))
      (node (ref "JP11") (pin "3") (pinfunction "3_3") (pintype "passive"))
      (node (ref "JP13") (pin "1") (pinfunction "1_1") (pintype "passive"))
      (node (ref "JP14") (pin "3") (pinfunction "3_3") (pintype "passive"))
      (node (ref "JP3") (pin "3") (pinfunction "3_3") (pintype "passive"))
      (node (ref "K5") (pin "6") (pinfunction "6_6") (pintype "passive"))
    )
    (net (code "36") (name "PB6") (class "Default")
      (node (ref "IC1") (pin "7") (pinfunction "(MISO/PCINT14)PB6_7") (pintype "bidirectional"))
      (node (ref "JP10") (pin "1") (pinfunction "1_1") (pintype "passive"))
      (node (ref "JP12") (pin "1") (pinfunction "1_1") (pintype "passive"))
      (node (ref "JP16") (pin "1") (pinfunction "1_1") (pintype "passive"))
    )
    (net (code "37") (name "PB6_DIP28") (class "Default")
      (node (ref "IC2") (pin "9") (pinfunction "PB6(XTAL1/TOSC1/PCINT6)_9") (pintype "bidirectional"))
      (node (ref "JP10") (pin "2") (pinfunction "2_2") (pintype "passive"))
    )
    (net (code "38") (name "PB7") (class "Default")
      (node (ref "IC1") (pin "8") (pinfunction "(SCK/PCINT15)PB7_8") (pintype "bidirectional"))
      (node (ref "JP11") (pin "1") (pinfunction "1_1") (pintype "passive"))
      (node (ref "JP15") (pin "1") (pinfunction "1_1") (pintype "passive"))
      (node (ref "JP9") (pin "1") (pinfunction "1_1") (pintype "passive"))
    )
    (net (code "39") (name "PB7_DIP28") (class "Default")
      (node (ref "IC2") (pin "10") (pinfunction "PB7(XTAL2/TOSC2/PCINT7)_10") (pintype "bidirectional"))
      (node (ref "JP9") (pin "2") (pinfunction "2_2") (pintype "passive"))
    )
    (net (code "40") (name "PC0") (class "Default")
      (node (ref "IC1") (pin "22") (pinfunction "(SCL/PCINT16)PC0_22") (pintype "bidirectional"))
      (node (ref "IC2") (pin "23") (pinfunction "PC0(ADC0/PCINT8)_23") (pintype "bidirectional"))
      (node (ref "JP4") (pin "3") (pinfunction "3_3") (pintype "passive"))
      (node (ref "K6") (pin "1") (pinfunction "1_1") (pintype "passive"))
    )
    (net (code "41") (name "PC1") (class "Default")
      (node (ref "IC1") (pin "23") (pinfunction "(SDA/PCINT17)PC1_23") (pintype "bidirectional"))
      (node (ref "IC2") (pin "24") (pinfunction "PC1(ADC1/PCINT9)_24") (pintype "bidirectional"))
      (node (ref "JP5") (pin "3") (pinfunction "3_3") (pintype "passive"))
      (node (ref "K6") (pin "2") (pinfunction "2_2") (pintype "passive"))
    )
    (net (code "42") (name "PC2") (class "Default")
      (node (ref "IC1") (pin "24") (pinfunction "(TCK/PCINT18)PC2_24") (pintype "bidirectional"))
      (node (ref "IC2") (pin "25") (pinfunction "PC2(ADC2/PCINT10)_25") (pintype "bidirectional"))
      (node (ref "JP6") (pin "3") (pinfunction "3_3") (pintype "passive"))
      (node (ref "K6") (pin "3") (pinfunction "3_3") (pintype "passive"))
    )
    (net (code "43") (name "PC3") (class "Default")
      (node (ref "IC1") (pin "25") (pinfunction "(TMS/PCINT19)PC3_25") (pintype "bidirectional"))
      (node (ref "IC2") (pin "26") (pinfunction "PC3(ADC3/PCINT11)_26") (pintype "bidirectional"))
      (node (ref "JP7") (pin "3") (pinfunction "3_3") (pintype "passive"))
      (node (ref "K6") (pin "4") (pinfunction "4_4") (pintype "passive"))
    )
    (net (code "44") (name "PC4") (class "Default")
      (node (ref "IC1") (pin "26") (pinfunction "(TDO/PCINT20)PC4_26") (pintype "bidirectional"))
      (node (ref "IC2") (pin "27") (pinfunction "PC4(ADC4/SDA/PCINT12)_27") (pintype "bidirectional"))
      (node (ref "JP1") (pin "3") (pinfunction "3_3") (pintype "passive"))
      (node (ref "K6") (pin "5") (pinfunction "5_5") (pintype "passive"))
    )
    (net (code "45") (name "PC5") (class "Default")
      (node (ref "IC1") (pin "27") (pinfunction "(TDI/PCINT21)PC5_27") (pintype "bidirectional"))
      (node (ref "IC2") (pin "28") (pinfunction "PC5(ADC5/SCLPCINT13)_28") (pintype "bidirectional"))
      (node (ref "JP3") (pin "1") (pinfunction "1_1") (pintype "passive"))
      (node (ref "K6") (pin "6") (pinfunction "6_6") (pintype "passive"))
      (node (ref "R1") (pin "2") (pinfunction "2_2") (pintype "passive"))
    )
    (net (code "46") (name "PC6") (class "Default")
      (node (ref "IC1") (pin "28") (pinfunction "(TOSC1/PCINT22)PC6_28") (pintype "bidirectional"))
      (node (ref "JP8") (pin "1") (pinfunction "1_1") (pintype "passive"))
      (node (ref "K1") (pin "10") (pinfunction "10_10") (pintype "passive"))
      (node (ref "R9") (pin "2") (pinfunction "2_2") (pintype "passive"))
    )
    (net (code "47") (name "PC6_DIP28") (class "Default")
      (node (ref "IC2") (pin "1") (pinfunction "PC6(/RESET/PCINT14)_1") (pintype "bidirectional"))
      (node (ref "JP8") (pin "2") (pinfunction "2_2") (pintype "passive"))
    )
    (net (code "48") (name "PC7") (class "Default")
      (node (ref "IC1") (pin "29") (pinfunction "(TOSC2/PCINT23)PC7_29") (pintype "bidirectional"))
      (node (ref "JP14") (pin "1") (pinfunction "1_1") (pintype "passive"))
      (node (ref "K1") (pin "9") (pinfunction "9_9") (pintype "passive"))
    )
    (net (code "49") (name "PD0{slash}RX") (class "Default")
      (node (ref "IC1") (pin "14") (pinfunction "(RXD0/PCINT24)PD0_14") (pintype "bidirectional"))
      (node (ref "IC2") (pin "2") (pinfunction "PD0(RXD/PCINT16)_2") (pintype "bidirectional"))
      (node (ref "K2") (pin "4") (pinfunction "4_4") (pintype "passive"))
      (node (ref "K4") (pin "1") (pinfunction "1_1") (pintype "passive"))
    )
    (net (code "50") (name "PD1{slash}TX") (class "Default")
      (node (ref "IC1") (pin "15") (pinfunction "(TXD0/PCINT25)PD1_15") (pintype "bidirectional"))
      (node (ref "IC2") (pin "3") (pinfunction "PD1(TXD/PCINT17)_3") (pintype "bidirectional"))
      (node (ref "K2") (pin "5") (pinfunction "5_5") (pintype "passive"))
      (node (ref "K4") (pin "2") (pinfunction "2_2") (pintype "passive"))
    )
    (net (code "51") (name "PD2") (class "Default")
      (node (ref "IC1") (pin "16") (pinfunction "(RXD1/INT0/PCINT26)PD2_16") (pintype "bidirectional"))
      (node (ref "IC2") (pin "4") (pinfunction "PD2(INT0/PCINT18)_4") (pintype "bidirectional"))
      (node (ref "JP15") (pin "3") (pinfunction "3_3") (pintype "passive"))
      (node (ref "K4") (pin "3") (pinfunction "3_3") (pintype "passive"))
    )
    (net (code "52") (name "PD3") (class "Default")
      (node (ref "IC1") (pin "17") (pinfunction "(TXD1/INT1/PCINT27)PD3_17") (pintype "bidirectional"))
      (node (ref "IC2") (pin "5") (pinfunction "PD3(INT1/OC2B/PCINT19)_5") (pintype "bidirectional"))
      (node (ref "JP16") (pin "3") (pinfunction "3_3") (pintype "passive"))
      (node (ref "K4") (pin "4") (pinfunction "4_4") (pintype "passive"))
    )
    (net (code "53") (name "PD4") (class "Default")
      (node (ref "IC1") (pin "18") (pinfunction "(XCK1/OC1B/PCINT28)PD4_18") (pintype "bidirectional"))
      (node (ref "IC2") (pin "6") (pinfunction "PD4(T0/XCK/PCINT20)_6") (pintype "bidirectional"))
      (node (ref "K4") (pin "5") (pinfunction "5_5") (pintype "passive"))
      (node (ref "K9") (pin "11") (pinfunction "DB4_11") (pintype "bidirectional"))
    )
    (net (code "54") (name "PD5") (class "Default")
      (node (ref "IC1") (pin "19") (pinfunction "(OC1A/PCINT29)PD5_19") (pintype "bidirectional"))
      (node (ref "IC2") (pin "11") (pinfunction "PD5(T1/OC0B/PCINT21)_11") (pintype "bidirectional"))
      (node (ref "K4") (pin "6") (pinfunction "6_6") (pintype "passive"))
      (node (ref "K9") (pin "12") (pinfunction "DB5_12") (pintype "bidirectional"))
    )
    (net (code "55") (name "PD6") (class "Default")
      (node (ref "IC1") (pin "20") (pinfunction "(OC2B/ICP/PCINT30)PD6_20") (pintype "bidirectional"))
      (node (ref "IC2") (pin "12") (pinfunction "PD6(AIN0/OC0A/PCINT22)_12") (pintype "bidirectional"))
      (node (ref "K4") (pin "7") (pinfunction "7_7") (pintype "passive"))
      (node (ref "K9") (pin "13") (pinfunction "DB6_13") (pintype "bidirectional"))
    )
    (net (code "56") (name "PD7") (class "Default")
      (node (ref "IC1") (pin "21") (pinfunction "(OC2A/PCINT31)PD7_21") (pintype "bidirectional"))
      (node (ref "IC2") (pin "13") (pinfunction "PD7(AIN1/PCINT23)_13") (pintype "bidirectional"))
      (node (ref "K4") (pin "8") (pinfunction "8_8") (pintype "passive"))
      (node (ref "K9") (pin "14") (pinfunction "DB7_14") (pintype "bidirectional"))
    )
    (net (code "57") (name "S1") (class "Default")
      (node (ref "JP4") (pin "2") (pinfunction "2_2") (pintype "passive"))
      (node (ref "K10") (pin "1") (pinfunction "1_1") (pintype "passive"))
      (node (ref "K11") (pin "1") (pinfunction "1_1") (pintype "passive"))
      (node (ref "R4") (pin "2") (pinfunction "2_2") (pintype "passive"))
      (node (ref "S1") (pin "1") (pinfunction "1_1") (pintype "passive"))
      (node (ref "S1A") (pin "1") (pinfunction "1_1") (pintype "passive"))
      (node (ref "S1B") (pin "1") (pinfunction "1_1") (pintype "passive"))
      (node (ref "S1C") (pin "1") (pinfunction "1_1") (pintype "passive"))
      (node (ref "S5") (pin "B") (pinfunction "B_B") (pintype "passive"))
      (node (ref "S5A") (pin "B") (pinfunction "B_B") (pintype "passive"))
      (node (ref "S5B") (pin "B") (pinfunction "B_B") (pintype "passive"))
      (node (ref "S5C") (pin "B") (pinfunction "B_B") (pintype "passive"))
    )
    (net (code "58") (name "S2") (class "Default")
      (node (ref "JP5") (pin "2") (pinfunction "2_2") (pintype "passive"))
      (node (ref "K10") (pin "2") (pinfunction "2_2") (pintype "passive"))
      (node (ref "K11") (pin "2") (pinfunction "2_2") (pintype "passive"))
      (node (ref "R5") (pin "1") (pinfunction "1_1") (pintype "passive"))
      (node (ref "S2") (pin "1") (pinfunction "1_1") (pintype "passive"))
      (node (ref "S2A") (pin "1") (pinfunction "1_1") (pintype "passive"))
      (node (ref "S2B") (pin "1") (pinfunction "1_1") (pintype "passive"))
      (node (ref "S2C") (pin "1") (pinfunction "1_1") (pintype "passive"))
      (node (ref "S5") (pin "A") (pinfunction "A_A") (pintype "passive"))
      (node (ref "S5A") (pin "A") (pinfunction "A_A") (pintype "passive"))
      (node (ref "S5B") (pin "A") (pinfunction "A_A") (pintype "passive"))
      (node (ref "S5C") (pin "A") (pinfunction "A_A") (pintype "passive"))
      (node (ref "S6") (pin "E") (pinfunction "2_E") (pintype "passive"))
      (node (ref "S6A") (pin "E") (pinfunction "2_E") (pintype "passive"))
      (node (ref "S6B") (pin "E") (pinfunction "2_E") (pintype "passive"))
      (node (ref "S6C") (pin "E") (pinfunction "2_E") (pintype "passive"))
    )
    (net (code "59") (name "S3") (class "Default")
      (node (ref "JP6") (pin "2") (pinfunction "2_2") (pintype "passive"))
      (node (ref "K10") (pin "3") (pinfunction "3_3") (pintype "passive"))
      (node (ref "K11") (pin "3") (pinfunction "3_3") (pintype "passive"))
      (node (ref "R6") (pin "2") (pinfunction "2_2") (pintype "passive"))
      (node (ref "S3") (pin "1") (pinfunction "1_1") (pintype "passive"))
      (node (ref "S3A") (pin "1") (pinfunction "1_1") (pintype "passive"))
      (node (ref "S3B") (pin "1") (pinfunction "1_1") (pintype "passive"))
      (node (ref "S3C") (pin "1") (pinfunction "1_1") (pintype "passive"))
      (node (ref "S5") (pin "E") (pinfunction "2_E") (pintype "passive"))
      (node (ref "S5A") (pin "E") (pinfunction "2_E") (pintype "passive"))
      (node (ref "S5B") (pin "E") (pinfunction "2_E") (pintype "passive"))
      (node (ref "S5C") (pin "E") (pinfunction "2_E") (pintype "passive"))
      (node (ref "S6") (pin "B") (pinfunction "B_B") (pintype "passive"))
      (node (ref "S6A") (pin "B") (pinfunction "B_B") (pintype "passive"))
      (node (ref "S6B") (pin "B") (pinfunction "B_B") (pintype "passive"))
      (node (ref "S6C") (pin "B") (pinfunction "B_B") (pintype "passive"))
    )
    (net (code "60") (name "S4") (class "Default")
      (node (ref "JP7") (pin "2") (pinfunction "2_2") (pintype "passive"))
      (node (ref "K10") (pin "4") (pinfunction "4_4") (pintype "passive"))
      (node (ref "K11") (pin "4") (pinfunction "4_4") (pintype "passive"))
      (node (ref "R7") (pin "1") (pinfunction "1_1") (pintype "passive"))
      (node (ref "S4") (pin "1") (pinfunction "1_1") (pintype "passive"))
      (node (ref "S4A") (pin "1") (pinfunction "1_1") (pintype "passive"))
      (node (ref "S4B") (pin "1") (pinfunction "1_1") (pintype "passive"))
      (node (ref "S4C") (pin "1") (pinfunction "1_1") (pintype "passive"))
      (node (ref "S6") (pin "A") (pinfunction "A_A") (pintype "passive"))
      (node (ref "S6A") (pin "A") (pinfunction "A_A") (pintype "passive"))
      (node (ref "S6B") (pin "A") (pinfunction "A_A") (pintype "passive"))
      (node (ref "S6C") (pin "A") (pinfunction "A_A") (pintype "passive"))
    )
    (net (code "61") (name "SCK") (class "Default")
      (node (ref "JP11") (pin "2") (pinfunction "2_2") (pintype "passive"))
      (node (ref "K3") (pin "3") (pinfunction "3_3") (pintype "passive"))
    )
    (net (code "62") (name "VCC") (class "Default")
      (node (ref "C3") (pin "1") (pinfunction "1_1") (pintype "passive"))
      (node (ref "C4") (pin "1") (pinfunction "1_1") (pintype "passive"))
      (node (ref "C8") (pin "+") (pinfunction "+_+") (pintype "passive"))
      (node (ref "D1") (pin "C") (pinfunction "C_C") (pintype "passive"))
      (node (ref "IC1") (pin "10") (pinfunction "VCC_10") (pintype "power_in"))
      (node (ref "IC2") (pin "7") (pinfunction "VCC_7") (pintype "power_in"))
      (node (ref "IC3") (pin "3") (pinfunction "VO_3") (pintype "passive"))
      (node (ref "IC4") (pin "2") (pinfunction "VI_2") (pintype "input"))
      (node (ref "K3") (pin "2") (pinfunction "2_2") (pintype "passive"))
      (node (ref "K7") (pin "3") (pinfunction "3_3") (pintype "passive"))
      (node (ref "K8") (pin "2") (pinfunction "2_2") (pintype "passive"))
      (node (ref "K9") (pin "2") (pinfunction "VDD_2") (pintype "power_in"))
      (node (ref "L1") (pin "1") (pinfunction "1_1") (pintype "passive"))
      (node (ref "P1") (pin "2") (pinfunction "2_2") (pintype "passive"))
      (node (ref "R10") (pin "2") (pinfunction "2_2") (pintype "passive"))
      (node (ref "R3") (pin "2") (pinfunction "2_2") (pintype "passive"))
      (node (ref "R4") (pin "1") (pinfunction "1_1") (pintype "passive"))
      (node (ref "R5") (pin "2") (pinfunction "2_2") (pintype "passive"))
      (node (ref "R6") (pin "1") (pinfunction "1_1") (pintype "passive"))
      (node (ref "R7") (pin "2") (pinfunction "2_2") (pintype "passive"))
    )
    (net (code "63") (name "VIN") (class "Default")
      (node (ref "C9") (pin "+") (pinfunction "+_+") (pintype "passive"))
      (node (ref "D2") (pin "C") (pinfunction "C_C") (pintype "passive"))
      (node (ref "IC3") (pin "1") (pinfunction "VI_1") (pintype "input"))
      (node (ref "K7") (pin "6") (pinfunction "6_6") (pintype "passive"))
    )
    (net (code "64") (name "XTAL1") (class "Default")
      (node (ref "C1") (pin "1") (pinfunction "1_1") (pintype "passive"))
      (node (ref "IC1") (pin "13") (pinfunction "XTAL1_13") (pintype "input"))
      (node (ref "JP10") (pin "3") (pinfunction "3_3") (pintype "passive"))
      (node (ref "X1") (pin "1") (pinfunction "1_1") (pintype "passive"))
    )
    (net (code "65") (name "XTAL2") (class "Default")
      (node (ref "C2") (pin "1") (pinfunction "1_1") (pintype "passive"))
      (node (ref "IC1") (pin "12") (pinfunction "XTAL2_12") (pintype "output"))
      (node (ref "JP9") (pin "3") (pinfunction "3_3") (pintype "passive"))
      (node (ref "X1") (pin "2") (pinfunction "2_2") (pintype "passive"))
    )
    (net (code "66") (name "unconnected-(K9-DB0-Pad7)") (class "Default")
      (node (ref "K9") (pin "7") (pinfunction "DB0_7") (pintype "bidirectional"))
    )
    (net (code "67") (name "unconnected-(K9-DB1-Pad8)") (class "Default")
      (node (ref "K9") (pin "8") (pinfunction "DB1_8") (pintype "bidirectional"))
    )
    (net (code "68") (name "unconnected-(K9-DB2-Pad9)") (class "Default")
      (node (ref "K9") (pin "9") (pinfunction "DB2_9") (pintype "bidirectional"))
    )
    (net (code "69") (name "unconnected-(K9-DB3-Pad10)") (class "Default")
      (node (ref "K9") (pin "10") (pinfunction "DB3_10") (pintype "bidirectional"))
    )
    (net (code "70") (name "unconnected-(S1-Pad2)") (class "Default")
      (node (ref "S1") (pin "2") (pinfunction "2_2") (pintype "passive"))
    )
    (net (code "71") (name "unconnected-(S1-Pad4)") (class "Default")
      (node (ref "S1") (pin "4") (pinfunction "4_4") (pintype "passive"))
    )
    (net (code "72") (name "unconnected-(S1A-Pad2)") (class "Default")
      (node (ref "S1A") (pin "2") (pinfunction "2_2") (pintype "passive"))
    )
    (net (code "73") (name "unconnected-(S1A-Pad4)") (class "Default")
      (node (ref "S1A") (pin "4") (pinfunction "4_4") (pintype "passive"))
    )
    (net (code "74") (name "unconnected-(S1B-Pad2)") (class "Default")
      (node (ref "S1B") (pin "2") (pinfunction "2_2") (pintype "passive"))
    )
    (net (code "75") (name "unconnected-(S1B-Pad4)") (class "Default")
      (node (ref "S1B") (pin "4") (pinfunction "4_4") (pintype "passive"))
    )
    (net (code "76") (name "unconnected-(S1C-Pad2)") (class "Default")
      (node (ref "S1C") (pin "2") (pinfunction "2_2") (pintype "passive"))
    )
    (net (code "77") (name "unconnected-(S1C-Pad4)") (class "Default")
      (node (ref "S1C") (pin "4") (pinfunction "4_4") (pintype "passive"))
    )
    (net (code "78") (name "unconnected-(S2-Pad2)") (class "Default")
      (node (ref "S2") (pin "2") (pinfunction "2_2") (pintype "passive"))
    )
    (net (code "79") (name "unconnected-(S2-Pad4)") (class "Default")
      (node (ref "S2") (pin "4") (pinfunction "4_4") (pintype "passive"))
    )
    (net (code "80") (name "unconnected-(S2A-Pad2)") (class "Default")
      (node (ref "S2A") (pin "2") (pinfunction "2_2") (pintype "passive"))
    )
    (net (code "81") (name "unconnected-(S2A-Pad4)") (class "Default")
      (node (ref "S2A") (pin "4") (pinfunction "4_4") (pintype "passive"))
    )
    (net (code "82") (name "unconnected-(S2B-Pad2)") (class "Default")
      (node (ref "S2B") (pin "2") (pinfunction "2_2") (pintype "passive"))
    )
    (net (code "83") (name "unconnected-(S2B-Pad4)") (class "Default")
      (node (ref "S2B") (pin "4") (pinfunction "4_4") (pintype "passive"))
    )
    (net (code "84") (name "unconnected-(S2C-Pad2)") (class "Default")
      (node (ref "S2C") (pin "2") (pinfunction "2_2") (pintype "passive"))
    )
    (net (code "85") (name "unconnected-(S2C-Pad4)") (class "Default")
      (node (ref "S2C") (pin "4") (pinfunction "4_4") (pintype "passive"))
    )
    (net (code "86") (name "unconnected-(S3-Pad2)") (class "Default")
      (node (ref "S3") (pin "2") (pinfunction "2_2") (pintype "passive"))
    )
    (net (code "87") (name "unconnected-(S3-Pad4)") (class "Default")
      (node (ref "S3") (pin "4") (pinfunction "4_4") (pintype "passive"))
    )
    (net (code "88") (name "unconnected-(S3A-Pad2)") (class "Default")
      (node (ref "S3A") (pin "2") (pinfunction "2_2") (pintype "passive"))
    )
    (net (code "89") (name "unconnected-(S3A-Pad4)") (class "Default")
      (node (ref "S3A") (pin "4") (pinfunction "4_4") (pintype "passive"))
    )
    (net (code "90") (name "unconnected-(S3B-Pad2)") (class "Default")
      (node (ref "S3B") (pin "2") (pinfunction "2_2") (pintype "passive"))
    )
    (net (code "91") (name "unconnected-(S3B-Pad4)") (class "Default")
      (node (ref "S3B") (pin "4") (pinfunction "4_4") (pintype "passive"))
    )
    (net (code "92") (name "unconnected-(S3C-Pad2)") (class "Default")
      (node (ref "S3C") (pin "2") (pinfunction "2_2") (pintype "passive"))
    )
    (net (code "93") (name "unconnected-(S3C-Pad4)") (class "Default")
      (node (ref "S3C") (pin "4") (pinfunction "4_4") (pintype "passive"))
    )
    (net (code "94") (name "unconnected-(S4-Pad2)") (class "Default")
      (node (ref "S4") (pin "2") (pinfunction "2_2") (pintype "passive"))
    )
    (net (code "95") (name "unconnected-(S4-Pad4)") (class "Default")
      (node (ref "S4") (pin "4") (pinfunction "4_4") (pintype "passive"))
    )
    (net (code "96") (name "unconnected-(S4A-Pad2)") (class "Default")
      (node (ref "S4A") (pin "2") (pinfunction "2_2") (pintype "passive"))
    )
    (net (code "97") (name "unconnected-(S4A-Pad4)") (class "Default")
      (node (ref "S4A") (pin "4") (pinfunction "4_4") (pintype "passive"))
    )
    (net (code "98") (name "unconnected-(S4B-Pad2)") (class "Default")
      (node (ref "S4B") (pin "2") (pinfunction "2_2") (pintype "passive"))
    )
    (net (code "99") (name "unconnected-(S4B-Pad4)") (class "Default")
      (node (ref "S4B") (pin "4") (pinfunction "4_4") (pintype "passive"))
    )
    (net (code "100") (name "unconnected-(S4C-Pad2)") (class "Default")
      (node (ref "S4C") (pin "2") (pinfunction "2_2") (pintype "passive"))
    )
    (net (code "101") (name "unconnected-(S4C-Pad4)") (class "Default")
      (node (ref "S4C") (pin "4") (pinfunction "4_4") (pintype "passive"))
    )
    (net (code "102") (name "~{RESET}") (class "Default")
      (node (ref "C10") (pin "2") (pinfunction "2_2") (pintype "passive"))
      (node (ref "IC1") (pin "9") (pinfunction "~{RESET}_9") (pintype "input"))
      (node (ref "JP8") (pin "3") (pinfunction "3_3") (pintype "passive"))
      (node (ref "K3") (pin "5") (pinfunction "5_5") (pintype "passive"))
      (node (ref "K7") (pin "1") (pinfunction "1_1") (pintype "passive"))
      (node (ref "R10") (pin "1") (pinfunction "1_1") (pintype "passive"))
    )
    (net (code "103") (name "~{RTS}") (class "Default")
      (node (ref "C10") (pin "1") (pinfunction "1_1") (pintype "passive"))
      (node (ref "K2") (pin "6") (pinfunction "6_6") (pintype "passive"))
    )
  )
)
